# mimuz-can-v030.net
KiCad netlist of a schematic drawn in EAGLE
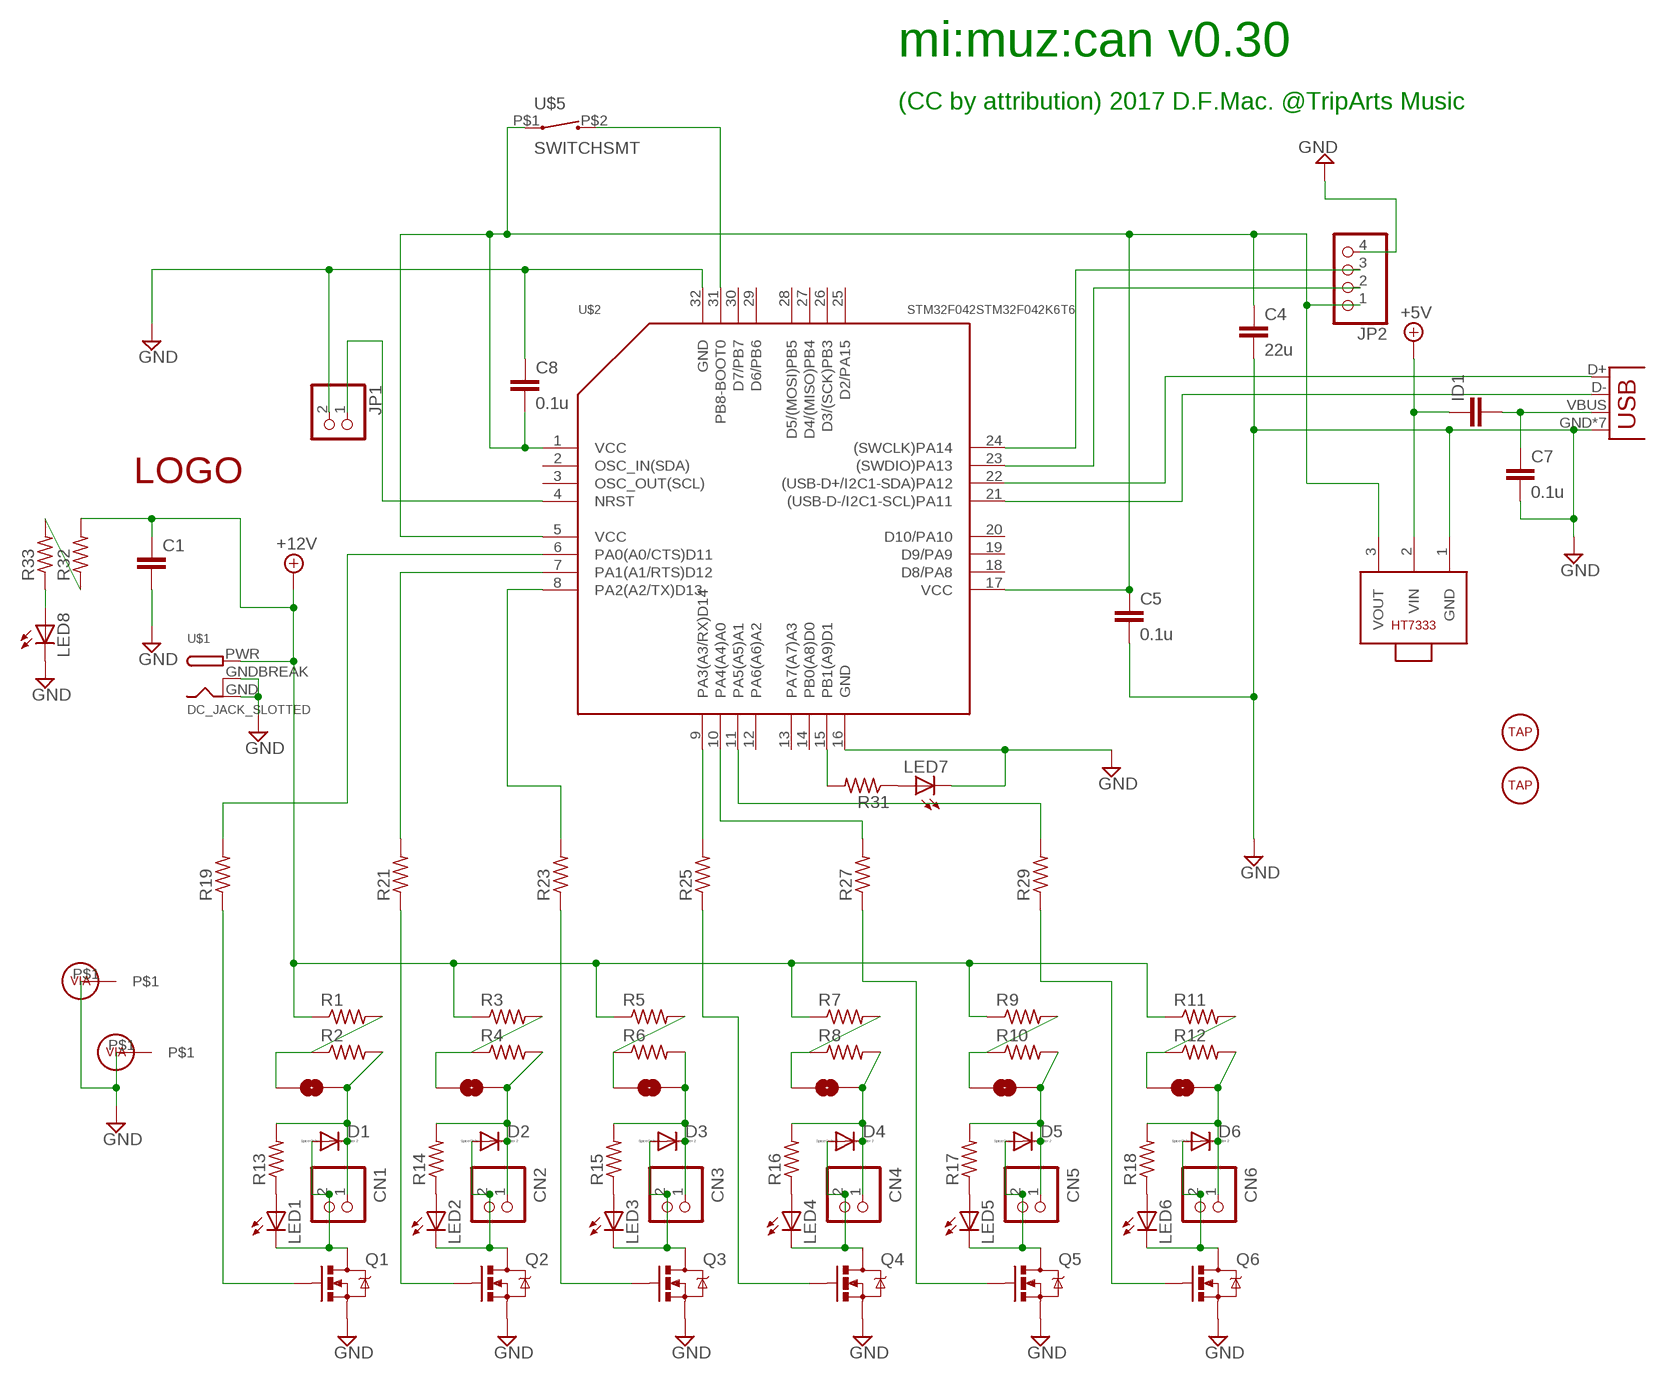
[diagram p0: schematic, sheet 1]

(export (version "E")
  (design (tool "Eeschema 10.0.6"))
  (components
    (comp (ref "C1")
      (value "C-EUC1206")
      (footprint "eagle-import:C1206")
      (libsource (lib "eagle-import") (part "C-EUC1206"))
    )
    (comp (ref "C4")
      (value "22u")
      (footprint "eagle-import:C0805")
      (libsource (lib "eagle-import") (part "C-EUC0805"))
    )
    (comp (ref "C5")
      (value "0.1u")
      (footprint "eagle-import:C0603")
      (libsource (lib "eagle-import") (part "C-EUC0603"))
    )
    (comp (ref "C7")
      (value "0.1u")
      (footprint "eagle-import:C0603")
      (libsource (lib "eagle-import") (part "C-EUC0603"))
    )
    (comp (ref "C8")
      (value "0.1u")
      (footprint "eagle-import:C0603")
      (libsource (lib "eagle-import") (part "C-EUC0603"))
    )
    (comp (ref "CN1")
      (value "B2B-PH-K-S")
      (footprint "eagle-import:B2B-PH-K-S")
      (libsource (lib "eagle-import") (part "B2B-PH-K-S"))
    )
    (comp (ref "CN2")
      (value "B2B-PH-K-S")
      (footprint "eagle-import:B2B-PH-K-S")
      (libsource (lib "eagle-import") (part "B2B-PH-K-S"))
    )
    (comp (ref "CN3")
      (value "B2B-PH-K-S")
      (footprint "eagle-import:B2B-PH-K-S")
      (libsource (lib "eagle-import") (part "B2B-PH-K-S"))
    )
    (comp (ref "CN4")
      (value "B2B-PH-K-S")
      (footprint "eagle-import:B2B-PH-K-S")
      (libsource (lib "eagle-import") (part "B2B-PH-K-S"))
    )
    (comp (ref "CN5")
      (value "B2B-PH-K-S")
      (footprint "eagle-import:B2B-PH-K-S")
      (libsource (lib "eagle-import") (part "B2B-PH-K-S"))
    )
    (comp (ref "CN6")
      (value "B2B-PH-K-S")
      (footprint "eagle-import:B2B-PH-K-S")
      (libsource (lib "eagle-import") (part "B2B-PH-K-S"))
    )
    (comp (ref "D1")
      (value "DIODE-DO214AC")
      (footprint "eagle-import:DO214AC")
      (libsource (lib "eagle-import") (part "DIODE-DO214AC"))
    )
    (comp (ref "D2")
      (value "DIODE-DO214AC")
      (footprint "eagle-import:DO214AC")
      (libsource (lib "eagle-import") (part "DIODE-DO214AC"))
    )
    (comp (ref "D3")
      (value "DIODE-DO214AC")
      (footprint "eagle-import:DO214AC")
      (libsource (lib "eagle-import") (part "DIODE-DO214AC"))
    )
    (comp (ref "D4")
      (value "DIODE-DO214AC")
      (footprint "eagle-import:DO214AC")
      (libsource (lib "eagle-import") (part "DIODE-DO214AC"))
    )
    (comp (ref "D5")
      (value "DIODE-DO214AC")
      (footprint "eagle-import:DO214AC")
      (libsource (lib "eagle-import") (part "DIODE-DO214AC"))
    )
    (comp (ref "D6")
      (value "DIODE-DO214AC")
      (footprint "eagle-import:DO214AC")
      (libsource (lib "eagle-import") (part "DIODE-DO214AC"))
    )
    (comp (ref "ID1")
      (value "C-EUC0805")
      (footprint "eagle-import:C0805")
      (libsource (lib "eagle-import") (part "C-EUC0805"))
    )
    (comp (ref "JP1")
      (value "PINHD-1X2")
      (footprint "eagle-import:1X02")
      (libsource (lib "eagle-import") (part "PINHD-1X2"))
    )
    (comp (ref "JP2")
      (value "PINHD-1X4")
      (footprint "eagle-import:1X04")
      (libsource (lib "eagle-import") (part "PINHD-1X4"))
    )
    (comp (ref "JP3")
      (value "JUMPER-SMT_2_NO_NO-SILK")
      (footprint "eagle-import:SMT-JUMPER_2_NO_NO-SILK")
      (libsource (lib "eagle-import") (part "JUMPER-SMT_2_NO_NO-SILK"))
    )
    (comp (ref "JP4")
      (value "USB-MICROB")
      (footprint "eagle-import:USB-MICROB")
      (libsource (lib "eagle-import") (part "USB-MICROB"))
    )
    (comp (ref "JP5")
      (value "JUMPER-SMT_2_NO_NO-SILK")
      (footprint "eagle-import:SMT-JUMPER_2_NO_NO-SILK")
      (libsource (lib "eagle-import") (part "JUMPER-SMT_2_NO_NO-SILK"))
    )
    (comp (ref "JP6")
      (value "JUMPER-SMT_2_NO_NO-SILK")
      (footprint "eagle-import:SMT-JUMPER_2_NO_NO-SILK")
      (libsource (lib "eagle-import") (part "JUMPER-SMT_2_NO_NO-SILK"))
    )
    (comp (ref "JP7")
      (value "JUMPER-SMT_2_NO_NO-SILK")
      (footprint "eagle-import:SMT-JUMPER_2_NO_NO-SILK")
      (libsource (lib "eagle-import") (part "JUMPER-SMT_2_NO_NO-SILK"))
    )
    (comp (ref "JP8")
      (value "JUMPER-SMT_2_NO_NO-SILK")
      (footprint "eagle-import:SMT-JUMPER_2_NO_NO-SILK")
      (libsource (lib "eagle-import") (part "JUMPER-SMT_2_NO_NO-SILK"))
    )
    (comp (ref "JP9")
      (value "JUMPER-SMT_2_NO_NO-SILK")
      (footprint "eagle-import:SMT-JUMPER_2_NO_NO-SILK")
      (libsource (lib "eagle-import") (part "JUMPER-SMT_2_NO_NO-SILK"))
    )
    (comp (ref "LED1")
      (value "LED3MM")
      (footprint "eagle-import:LED3MM")
      (libsource (lib "eagle-import") (part "LED3MM"))
    )
    (comp (ref "LED2")
      (value "LED3MM")
      (footprint "eagle-import:LED3MM")
      (libsource (lib "eagle-import") (part "LED3MM"))
    )
    (comp (ref "LED3")
      (value "LED3MM")
      (footprint "eagle-import:LED3MM")
      (libsource (lib "eagle-import") (part "LED3MM"))
    )
    (comp (ref "LED4")
      (value "LED3MM")
      (footprint "eagle-import:LED3MM")
      (libsource (lib "eagle-import") (part "LED3MM"))
    )
    (comp (ref "LED5")
      (value "LED3MM")
      (footprint "eagle-import:LED3MM")
      (libsource (lib "eagle-import") (part "LED3MM"))
    )
    (comp (ref "LED6")
      (value "LED3MM")
      (footprint "eagle-import:LED3MM")
      (libsource (lib "eagle-import") (part "LED3MM"))
    )
    (comp (ref "LED7")
      (value "LED3MM")
      (footprint "eagle-import:LED3MM")
      (libsource (lib "eagle-import") (part "LED3MM"))
    )
    (comp (ref "LED8")
      (value "LED3MM")
      (footprint "eagle-import:LED3MM")
      (libsource (lib "eagle-import") (part "LED3MM"))
    )
    (comp (ref "Q1")
      (value "MOSFET-NCHANNELSMD")
      (footprint "eagle-import:SOT23-3")
      (libsource (lib "eagle-import") (part "MOSFET-NCHANNELSMD"))
    )
    (comp (ref "Q2")
      (value "MOSFET-NCHANNELSMD")
      (footprint "eagle-import:SOT23-3")
      (libsource (lib "eagle-import") (part "MOSFET-NCHANNELSMD"))
    )
    (comp (ref "Q3")
      (value "MOSFET-NCHANNELSMD")
      (footprint "eagle-import:SOT23-3")
      (libsource (lib "eagle-import") (part "MOSFET-NCHANNELSMD"))
    )
    (comp (ref "Q4")
      (value "MOSFET-NCHANNELSMD")
      (footprint "eagle-import:SOT23-3")
      (libsource (lib "eagle-import") (part "MOSFET-NCHANNELSMD"))
    )
    (comp (ref "Q5")
      (value "MOSFET-NCHANNELSMD")
      (footprint "eagle-import:SOT23-3")
      (libsource (lib "eagle-import") (part "MOSFET-NCHANNELSMD"))
    )
    (comp (ref "Q6")
      (value "MOSFET-NCHANNELSMD")
      (footprint "eagle-import:SOT23-3")
      (libsource (lib "eagle-import") (part "MOSFET-NCHANNELSMD"))
    )
    (comp (ref "R1")
      (value "R-US_R2512")
      (footprint "eagle-import:R2512")
      (libsource (lib "eagle-import") (part "R-US_R2512"))
    )
    (comp (ref "R2")
      (value "R-US_R2512")
      (footprint "eagle-import:R2512")
      (libsource (lib "eagle-import") (part "R-US_R2512"))
    )
    (comp (ref "R3")
      (value "R-US_R2512")
      (footprint "eagle-import:R2512")
      (libsource (lib "eagle-import") (part "R-US_R2512"))
    )
    (comp (ref "R4")
      (value "R-US_R2512")
      (footprint "eagle-import:R2512")
      (libsource (lib "eagle-import") (part "R-US_R2512"))
    )
    (comp (ref "R5")
      (value "R-US_R2512")
      (footprint "eagle-import:R2512")
      (libsource (lib "eagle-import") (part "R-US_R2512"))
    )
    (comp (ref "R6")
      (value "R-US_R2512")
      (footprint "eagle-import:R2512")
      (libsource (lib "eagle-import") (part "R-US_R2512"))
    )
    (comp (ref "R7")
      (value "R-US_R2512")
      (footprint "eagle-import:R2512")
      (libsource (lib "eagle-import") (part "R-US_R2512"))
    )
    (comp (ref "R8")
      (value "R-US_R2512")
      (footprint "eagle-import:R2512")
      (libsource (lib "eagle-import") (part "R-US_R2512"))
    )
    (comp (ref "R9")
      (value "R-US_R2512")
      (footprint "eagle-import:R2512")
      (libsource (lib "eagle-import") (part "R-US_R2512"))
    )
    (comp (ref "R10")
      (value "R-US_R2512")
      (footprint "eagle-import:R2512")
      (libsource (lib "eagle-import") (part "R-US_R2512"))
    )
    (comp (ref "R11")
      (value "R-US_R2512")
      (footprint "eagle-import:R2512")
      (libsource (lib "eagle-import") (part "R-US_R2512"))
    )
    (comp (ref "R12")
      (value "R-US_R2512")
      (footprint "eagle-import:R2512")
      (libsource (lib "eagle-import") (part "R-US_R2512"))
    )
    (comp (ref "R13")
      (value "R-US_R0805")
      (footprint "eagle-import:R0805")
      (libsource (lib "eagle-import") (part "R-US_R0805"))
    )
    (comp (ref "R14")
      (value "R-US_R0805")
      (footprint "eagle-import:R0805")
      (libsource (lib "eagle-import") (part "R-US_R0805"))
    )
    (comp (ref "R15")
      (value "R-US_R0805")
      (footprint "eagle-import:R0805")
      (libsource (lib "eagle-import") (part "R-US_R0805"))
    )
    (comp (ref "R16")
      (value "R-US_R0805")
      (footprint "eagle-import:R0805")
      (libsource (lib "eagle-import") (part "R-US_R0805"))
    )
    (comp (ref "R17")
      (value "R-US_R0805")
      (footprint "eagle-import:R0805")
      (libsource (lib "eagle-import") (part "R-US_R0805"))
    )
    (comp (ref "R18")
      (value "R-US_R0805")
      (footprint "eagle-import:R0805")
      (libsource (lib "eagle-import") (part "R-US_R0805"))
    )
    (comp (ref "R19")
      (value "R-US_R0603")
      (footprint "eagle-import:R0603")
      (libsource (lib "eagle-import") (part "R-US_R0603"))
    )
    (comp (ref "R21")
      (value "R-US_R0603")
      (footprint "eagle-import:R0603")
      (libsource (lib "eagle-import") (part "R-US_R0603"))
    )
    (comp (ref "R23")
      (value "R-US_R0603")
      (footprint "eagle-import:R0603")
      (libsource (lib "eagle-import") (part "R-US_R0603"))
    )
    (comp (ref "R25")
      (value "R-US_R0603")
      (footprint "eagle-import:R0603")
      (libsource (lib "eagle-import") (part "R-US_R0603"))
    )
    (comp (ref "R27")
      (value "R-US_R0603")
      (footprint "eagle-import:R0603")
      (libsource (lib "eagle-import") (part "R-US_R0603"))
    )
    (comp (ref "R29")
      (value "R-US_R0603")
      (footprint "eagle-import:R0603")
      (libsource (lib "eagle-import") (part "R-US_R0603"))
    )
    (comp (ref "R31")
      (value "R-US_R0603")
      (footprint "eagle-import:R0603")
      (libsource (lib "eagle-import") (part "R-US_R0603"))
    )
    (comp (ref "R32")
      (value "R-US_R0805")
      (footprint "eagle-import:R0805")
      (libsource (lib "eagle-import") (part "R-US_R0805"))
    )
    (comp (ref "R33")
      (value "R-US_R0805")
      (footprint "eagle-import:R0805")
      (libsource (lib "eagle-import") (part "R-US_R0805"))
    )
    (comp (ref "U$1")
      (value "DC_JACK_SLOTTED")
      (footprint "eagle-import:DC_JACK_SLOTTED")
      (libsource (lib "eagle-import") (part "DC_JACK_SLOTTED"))
    )
    (comp (ref "U$2")
      (value "STM32F042STM32F042K6T6")
      (footprint "eagle-import:TQFP32")
      (libsource (lib "eagle-import") (part "STM32F042STM32F042K6T6"))
    )
    (comp (ref "U$3")
      (value "TAPHOLE")
      (footprint "eagle-import:TAPHOLE-3MM")
      (libsource (lib "eagle-import") (part "TAPHOLE"))
    )
    (comp (ref "U$4")
      (value "VIA")
      (footprint "eagle-import:VIA")
      (libsource (lib "eagle-import") (part "VIA"))
    )
    (comp (ref "U$5")
      (value "SWITCHSMT")
      (footprint "eagle-import:SWITCH-SMT-2_4_3")
      (libsource (lib "eagle-import") (part "SWITCHSMT"))
    )
    (comp (ref "U$6")
      (value "TAPHOLE")
      (footprint "eagle-import:TAPHOLE-3MM")
      (libsource (lib "eagle-import") (part "TAPHOLE"))
    )
    (comp (ref "U$7")
      (value "VIA")
      (footprint "eagle-import:VIA")
      (libsource (lib "eagle-import") (part "VIA"))
    )
    (comp (ref "U$12")
      (value "LOGOSMALL")
      (footprint "eagle-import:LOGO-SMALL")
      (libsource (lib "eagle-import") (part "LOGOSMALL"))
    )
    (comp (ref "U$14")
      (value "HT7333")
      (footprint "eagle-import:SOT89")
      (libsource (lib "eagle-import") (part "HT7333"))
    )
  )
  (nets
    (net (code "1") (name "+5V") (class "Default")
      (node (ref "ID1") (pin "1") (pinfunction "1_1") (pintype "passive"))
      (node (ref "U$14") (pin "2") (pinfunction "VIN_2") (pintype "bidirectional"))
    )
    (net (code "2") (name "+12V") (class "Default")
      (node (ref "C1") (pin "1") (pinfunction "1_1") (pintype "passive"))
      (node (ref "R1") (pin "1") (pinfunction "1_1") (pintype "passive"))
      (node (ref "R11") (pin "1") (pinfunction "1_1") (pintype "passive"))
      (node (ref "R3") (pin "1") (pinfunction "1_1") (pintype "passive"))
      (node (ref "R32") (pin "2") (pinfunction "2_2") (pintype "passive"))
      (node (ref "R5") (pin "1") (pinfunction "1_1") (pintype "passive"))
      (node (ref "R7") (pin "1") (pinfunction "1_1") (pintype "passive"))
      (node (ref "R9") (pin "1") (pinfunction "1_1") (pintype "passive"))
      (node (ref "U$1") (pin "PWR") (pinfunction "PWR_PWR") (pintype "power_in"))
    )
    (net (code "3") (name "GND") (class "Default")
      (node (ref "C1") (pin "2") (pinfunction "2_2") (pintype "passive"))
      (node (ref "C4") (pin "2") (pinfunction "2_2") (pintype "passive"))
      (node (ref "C5") (pin "2") (pinfunction "2_2") (pintype "passive"))
      (node (ref "C7") (pin "2") (pinfunction "2_2") (pintype "passive"))
      (node (ref "C8") (pin "1") (pinfunction "1_1") (pintype "passive"))
      (node (ref "JP1") (pin "2") (pinfunction "2_2") (pintype "passive"))
      (node (ref "JP2") (pin "4") (pinfunction "4_4") (pintype "passive"))
      (node (ref "JP4") (pin "GND") (pinfunction "GND_GND") (pintype "bidirectional"))
      (node (ref "JP4") (pin "MT1") (pinfunction "GND_MT1") (pintype "bidirectional"))
      (node (ref "JP4") (pin "MT3") (pinfunction "GND_MT3") (pintype "bidirectional"))
      (node (ref "JP4") (pin "P$2") (pinfunction "GND_P$2") (pintype "bidirectional"))
      (node (ref "JP4") (pin "P$4") (pinfunction "GND_P$4") (pintype "bidirectional"))
      (node (ref "JP4") (pin "P$5") (pinfunction "GND_P$5") (pintype "bidirectional"))
      (node (ref "JP4") (pin "P$6") (pinfunction "GND_P$6") (pintype "bidirectional"))
      (node (ref "LED7") (pin "K") (pinfunction "C_K") (pintype "passive"))
      (node (ref "LED8") (pin "K") (pinfunction "C_K") (pintype "passive"))
      (node (ref "Q1") (pin "2") (pinfunction "S_2") (pintype "passive"))
      (node (ref "Q2") (pin "2") (pinfunction "S_2") (pintype "passive"))
      (node (ref "Q3") (pin "2") (pinfunction "S_2") (pintype "passive"))
      (node (ref "Q4") (pin "2") (pinfunction "S_2") (pintype "passive"))
      (node (ref "Q5") (pin "2") (pinfunction "S_2") (pintype "passive"))
      (node (ref "Q6") (pin "2") (pinfunction "S_2") (pintype "passive"))
      (node (ref "U$1") (pin "GND") (pinfunction "GND_GND") (pintype "power_in"))
      (node (ref "U$1") (pin "GNDBREAK") (pinfunction "GNDBREAK_GNDBREAK") (pintype "power_in"))
      (node (ref "U$14") (pin "1") (pinfunction "GND_1") (pintype "bidirectional"))
      (node (ref "U$2") (pin "16") (pinfunction "GND_16") (pintype "bidirectional"))
      (node (ref "U$2") (pin "32") (pinfunction "GND_32") (pintype "bidirectional"))
      (node (ref "U$4") (pin "P$1") (pinfunction "P$1_P$1") (pintype "bidirectional"))
      (node (ref "U$7") (pin "P$1") (pinfunction "P$1_P$1") (pintype "bidirectional"))
    )
    (net (code "4") (name "Net-(C7-Pad1)") (class "Default")
      (node (ref "C7") (pin "1") (pinfunction "1_1") (pintype "passive"))
      (node (ref "ID1") (pin "2") (pinfunction "2_2") (pintype "passive"))
      (node (ref "JP4") (pin "VBUS") (pinfunction "VBUS_VBUS") (pintype "bidirectional"))
    )
    (net (code "5") (name "Net-(CN1-Pad1)") (class "Default")
      (node (ref "CN1") (pin "1") (pinfunction "1_1") (pintype "passive"))
      (node (ref "D1") (pin "C") (pinfunction "C_C") (pintype "passive"))
      (node (ref "JP3") (pin "2") (pinfunction "2_2") (pintype "passive"))
      (node (ref "R13") (pin "2") (pinfunction "2_2") (pintype "passive"))
      (node (ref "R2") (pin "2") (pinfunction "2_2") (pintype "passive"))
    )
    (net (code "6") (name "Net-(CN2-Pad1)") (class "Default")
      (node (ref "CN2") (pin "1") (pinfunction "1_1") (pintype "passive"))
      (node (ref "D2") (pin "C") (pinfunction "C_C") (pintype "passive"))
      (node (ref "JP5") (pin "2") (pinfunction "2_2") (pintype "passive"))
      (node (ref "R14") (pin "2") (pinfunction "2_2") (pintype "passive"))
      (node (ref "R4") (pin "2") (pinfunction "2_2") (pintype "passive"))
    )
    (net (code "7") (name "Net-(CN3-Pad1)") (class "Default")
      (node (ref "CN3") (pin "1") (pinfunction "1_1") (pintype "passive"))
      (node (ref "D3") (pin "C") (pinfunction "C_C") (pintype "passive"))
      (node (ref "JP6") (pin "2") (pinfunction "2_2") (pintype "passive"))
      (node (ref "R15") (pin "2") (pinfunction "2_2") (pintype "passive"))
      (node (ref "R6") (pin "2") (pinfunction "2_2") (pintype "passive"))
    )
    (net (code "8") (name "Net-(CN4-Pad1)") (class "Default")
      (node (ref "CN4") (pin "1") (pinfunction "1_1") (pintype "passive"))
      (node (ref "D4") (pin "C") (pinfunction "C_C") (pintype "passive"))
      (node (ref "JP7") (pin "2") (pinfunction "2_2") (pintype "passive"))
      (node (ref "R16") (pin "2") (pinfunction "2_2") (pintype "passive"))
      (node (ref "R8") (pin "2") (pinfunction "2_2") (pintype "passive"))
    )
    (net (code "9") (name "Net-(CN5-Pad1)") (class "Default")
      (node (ref "CN5") (pin "1") (pinfunction "1_1") (pintype "passive"))
      (node (ref "D5") (pin "C") (pinfunction "C_C") (pintype "passive"))
      (node (ref "JP8") (pin "2") (pinfunction "2_2") (pintype "passive"))
      (node (ref "R10") (pin "2") (pinfunction "2_2") (pintype "passive"))
      (node (ref "R17") (pin "2") (pinfunction "2_2") (pintype "passive"))
    )
    (net (code "10") (name "Net-(CN6-Pad1)") (class "Default")
      (node (ref "CN6") (pin "1") (pinfunction "1_1") (pintype "passive"))
      (node (ref "D6") (pin "C") (pinfunction "C_C") (pintype "passive"))
      (node (ref "JP9") (pin "2") (pinfunction "2_2") (pintype "passive"))
      (node (ref "R12") (pin "2") (pinfunction "2_2") (pintype "passive"))
      (node (ref "R18") (pin "2") (pinfunction "2_2") (pintype "passive"))
    )
    (net (code "11") (name "Net-(JP3-Pad1)") (class "Default")
      (node (ref "JP3") (pin "1") (pinfunction "1_1") (pintype "passive"))
      (node (ref "R1") (pin "2") (pinfunction "2_2") (pintype "passive"))
      (node (ref "R2") (pin "1") (pinfunction "1_1") (pintype "passive"))
    )
    (net (code "12") (name "Net-(JP5-Pad1)") (class "Default")
      (node (ref "JP5") (pin "1") (pinfunction "1_1") (pintype "passive"))
      (node (ref "R3") (pin "2") (pinfunction "2_2") (pintype "passive"))
      (node (ref "R4") (pin "1") (pinfunction "1_1") (pintype "passive"))
    )
    (net (code "13") (name "Net-(JP6-Pad1)") (class "Default")
      (node (ref "JP6") (pin "1") (pinfunction "1_1") (pintype "passive"))
      (node (ref "R5") (pin "2") (pinfunction "2_2") (pintype "passive"))
      (node (ref "R6") (pin "1") (pinfunction "1_1") (pintype "passive"))
    )
    (net (code "14") (name "Net-(JP7-Pad1)") (class "Default")
      (node (ref "JP7") (pin "1") (pinfunction "1_1") (pintype "passive"))
      (node (ref "R7") (pin "2") (pinfunction "2_2") (pintype "passive"))
      (node (ref "R8") (pin "1") (pinfunction "1_1") (pintype "passive"))
    )
    (net (code "15") (name "Net-(JP8-Pad1)") (class "Default")
      (node (ref "JP8") (pin "1") (pinfunction "1_1") (pintype "passive"))
      (node (ref "R10") (pin "1") (pinfunction "1_1") (pintype "passive"))
      (node (ref "R9") (pin "2") (pinfunction "2_2") (pintype "passive"))
    )
    (net (code "16") (name "Net-(JP9-Pad1)") (class "Default")
      (node (ref "JP9") (pin "1") (pinfunction "1_1") (pintype "passive"))
      (node (ref "R11") (pin "2") (pinfunction "2_2") (pintype "passive"))
      (node (ref "R12") (pin "1") (pinfunction "1_1") (pintype "passive"))
    )
    (net (code "17") (name "Net-(LED1-C)") (class "Default")
      (node (ref "CN1") (pin "2") (pinfunction "2_2") (pintype "passive"))
      (node (ref "D1") (pin "A") (pinfunction "A_A") (pintype "passive"))
      (node (ref "LED1") (pin "K") (pinfunction "C_K") (pintype "passive"))
      (node (ref "Q1") (pin "3") (pinfunction "D_3") (pintype "passive"))
    )
    (net (code "18") (name "Net-(LED1-PadA)") (class "Default")
      (node (ref "LED1") (pin "A") (pinfunction "A_A") (pintype "passive"))
      (node (ref "R13") (pin "1") (pinfunction "1_1") (pintype "passive"))
    )
    (net (code "19") (name "Net-(LED2-C)") (class "Default")
      (node (ref "CN2") (pin "2") (pinfunction "2_2") (pintype "passive"))
      (node (ref "D2") (pin "A") (pinfunction "A_A") (pintype "passive"))
      (node (ref "LED2") (pin "K") (pinfunction "C_K") (pintype "passive"))
      (node (ref "Q2") (pin "3") (pinfunction "D_3") (pintype "passive"))
    )
    (net (code "20") (name "Net-(LED2-PadA)") (class "Default")
      (node (ref "LED2") (pin "A") (pinfunction "A_A") (pintype "passive"))
      (node (ref "R14") (pin "1") (pinfunction "1_1") (pintype "passive"))
    )
    (net (code "21") (name "Net-(LED3-C)") (class "Default")
      (node (ref "CN3") (pin "2") (pinfunction "2_2") (pintype "passive"))
      (node (ref "D3") (pin "A") (pinfunction "A_A") (pintype "passive"))
      (node (ref "LED3") (pin "K") (pinfunction "C_K") (pintype "passive"))
      (node (ref "Q3") (pin "3") (pinfunction "D_3") (pintype "passive"))
    )
    (net (code "22") (name "Net-(LED3-PadA)") (class "Default")
      (node (ref "LED3") (pin "A") (pinfunction "A_A") (pintype "passive"))
      (node (ref "R15") (pin "1") (pinfunction "1_1") (pintype "passive"))
    )
    (net (code "23") (name "Net-(LED4-C)") (class "Default")
      (node (ref "CN4") (pin "2") (pinfunction "2_2") (pintype "passive"))
      (node (ref "D4") (pin "A") (pinfunction "A_A") (pintype "passive"))
      (node (ref "LED4") (pin "K") (pinfunction "C_K") (pintype "passive"))
      (node (ref "Q4") (pin "3") (pinfunction "D_3") (pintype "passive"))
    )
    (net (code "24") (name "Net-(LED4-PadA)") (class "Default")
      (node (ref "LED4") (pin "A") (pinfunction "A_A") (pintype "passive"))
      (node (ref "R16") (pin "1") (pinfunction "1_1") (pintype "passive"))
    )
    (net (code "25") (name "Net-(LED5-C)") (class "Default")
      (node (ref "CN5") (pin "2") (pinfunction "2_2") (pintype "passive"))
      (node (ref "D5") (pin "A") (pinfunction "A_A") (pintype "passive"))
      (node (ref "LED5") (pin "K") (pinfunction "C_K") (pintype "passive"))
      (node (ref "Q5") (pin "3") (pinfunction "D_3") (pintype "passive"))
    )
    (net (code "26") (name "Net-(LED5-PadA)") (class "Default")
      (node (ref "LED5") (pin "A") (pinfunction "A_A") (pintype "passive"))
      (node (ref "R17") (pin "1") (pinfunction "1_1") (pintype "passive"))
    )
    (net (code "27") (name "Net-(LED6-C)") (class "Default")
      (node (ref "CN6") (pin "2") (pinfunction "2_2") (pintype "passive"))
      (node (ref "D6") (pin "A") (pinfunction "A_A") (pintype "passive"))
      (node (ref "LED6") (pin "K") (pinfunction "C_K") (pintype "passive"))
      (node (ref "Q6") (pin "3") (pinfunction "D_3") (pintype "passive"))
    )
    (net (code "28") (name "Net-(LED6-PadA)") (class "Default")
      (node (ref "LED6") (pin "A") (pinfunction "A_A") (pintype "passive"))
      (node (ref "R18") (pin "1") (pinfunction "1_1") (pintype "passive"))
    )
    (net (code "29") (name "Net-(LED7-PadA)") (class "Default")
      (node (ref "LED7") (pin "A") (pinfunction "A_A") (pintype "passive"))
      (node (ref "R31") (pin "1") (pinfunction "1_1") (pintype "passive"))
    )
    (net (code "30") (name "Net-(LED8-PadA)") (class "Default")
      (node (ref "LED8") (pin "A") (pinfunction "A_A") (pintype "passive"))
      (node (ref "R33") (pin "1") (pinfunction "1_1") (pintype "passive"))
    )
    (net (code "31") (name "Net-(Q1-G)") (class "Default")
      (node (ref "Q1") (pin "1") (pinfunction "G_1") (pintype "passive"))
      (node (ref "R19") (pin "1") (pinfunction "1_1") (pintype "passive"))
    )
    (net (code "32") (name "Net-(Q2-G)") (class "Default")
      (node (ref "Q2") (pin "1") (pinfunction "G_1") (pintype "passive"))
      (node (ref "R21") (pin "1") (pinfunction "1_1") (pintype "passive"))
    )
    (net (code "33") (name "Net-(Q3-G)") (class "Default")
      (node (ref "Q3") (pin "1") (pinfunction "G_1") (pintype "passive"))
      (node (ref "R23") (pin "1") (pinfunction "1_1") (pintype "passive"))
    )
    (net (code "34") (name "Net-(Q4-G)") (class "Default")
      (node (ref "Q4") (pin "1") (pinfunction "G_1") (pintype "passive"))
      (node (ref "R25") (pin "1") (pinfunction "1_1") (pintype "passive"))
    )
    (net (code "35") (name "Net-(Q5-G)") (class "Default")
      (node (ref "Q5") (pin "1") (pinfunction "G_1") (pintype "passive"))
      (node (ref "R27") (pin "1") (pinfunction "1_1") (pintype "passive"))
    )
    (net (code "36") (name "Net-(Q6-G)") (class "Default")
      (node (ref "Q6") (pin "1") (pinfunction "G_1") (pintype "passive"))
      (node (ref "R29") (pin "1") (pinfunction "1_1") (pintype "passive"))
    )
    (net (code "37") (name "Net-(R32-Pad1)") (class "Default")
      (node (ref "R32") (pin "1") (pinfunction "1_1") (pintype "passive"))
      (node (ref "R33") (pin "2") (pinfunction "2_2") (pintype "passive"))
    )
    (net (code "38") (name "Net-(U$2-(SWCLK)PA14)") (class "Default")
      (node (ref "JP2") (pin "3") (pinfunction "3_3") (pintype "passive"))
      (node (ref "U$2") (pin "24") (pinfunction "(SWCLK)PA14_24") (pintype "bidirectional"))
    )
    (net (code "39") (name "Net-(U$2-(SWDIO)PA13)") (class "Default")
      (node (ref "JP2") (pin "2") (pinfunction "2_2") (pintype "passive"))
      (node (ref "U$2") (pin "23") (pinfunction "(SWDIO)PA13_23") (pintype "bidirectional"))
    )
    (net (code "40") (name "Net-(U$2-(USB-D+{slash}I2C1-SDA)PA12)") (class "Default")
      (node (ref "JP4") (pin "D+") (pinfunction "D+_D+") (pintype "bidirectional"))
      (node (ref "U$2") (pin "22") (pinfunction "(USB-D+/I2C1-SDA)PA12_22") (pintype "bidirectional"))
    )
    (net (code "41") (name "Net-(U$2-(USB-D-{slash}I2C1-SCL)PA11)") (class "Default")
      (node (ref "JP4") (pin "D-") (pinfunction "D-_D-") (pintype "bidirectional"))
      (node (ref "U$2") (pin "21") (pinfunction "(USB-D-/I2C1-SCL)PA11_21") (pintype "bidirectional"))
    )
    (net (code "42") (name "Net-(U$2-NRST)") (class "Default")
      (node (ref "JP1") (pin "1") (pinfunction "1_1") (pintype "passive"))
      (node (ref "U$2") (pin "4") (pinfunction "NRST_4") (pintype "bidirectional"))
    )
    (net (code "43") (name "Net-(U$2-PA0(A0{slash}CTS)D11)") (class "Default")
      (node (ref "R19") (pin "2") (pinfunction "2_2") (pintype "passive"))
      (node (ref "U$2") (pin "6") (pinfunction "PA0(A0/CTS)D11_6") (pintype "bidirectional"))
    )
    (net (code "44") (name "Net-(U$2-PA1(A1{slash}RTS)D12)") (class "Default")
      (node (ref "R21") (pin "2") (pinfunction "2_2") (pintype "passive"))
      (node (ref "U$2") (pin "7") (pinfunction "PA1(A1/RTS)D12_7") (pintype "bidirectional"))
    )
    (net (code "45") (name "Net-(U$2-PA2(A2{slash}TX)D13)") (class "Default")
      (node (ref "R23") (pin "2") (pinfunction "2_2") (pintype "passive"))
      (node (ref "U$2") (pin "8") (pinfunction "PA2(A2/TX)D13_8") (pintype "bidirectional"))
    )
    (net (code "46") (name "Net-(U$2-PA3(A3{slash}RX)D14)") (class "Default")
      (node (ref "R25") (pin "2") (pinfunction "2_2") (pintype "passive"))
      (node (ref "U$2") (pin "9") (pinfunction "PA3(A3/RX)D14_9") (pintype "bidirectional"))
    )
    (net (code "47") (name "Net-(U$2-PA4(A4)A0)") (class "Default")
      (node (ref "R27") (pin "2") (pinfunction "2_2") (pintype "passive"))
      (node (ref "U$2") (pin "10") (pinfunction "PA4(A4)A0_10") (pintype "bidirectional"))
    )
    (net (code "48") (name "Net-(U$2-PA5(A5)A1)") (class "Default")
      (node (ref "R29") (pin "2") (pinfunction "2_2") (pintype "passive"))
      (node (ref "U$2") (pin "11") (pinfunction "PA5(A5)A1_11") (pintype "bidirectional"))
    )
    (net (code "49") (name "Net-(U$2-PB1(A9)D1)") (class "Default")
      (node (ref "R31") (pin "2") (pinfunction "2_2") (pintype "passive"))
      (node (ref "U$2") (pin "15") (pinfunction "PB1(A9)D1_15") (pintype "bidirectional"))
    )
    (net (code "50") (name "Net-(U$2-PB8-BOOT0)") (class "Default")
      (node (ref "U$2") (pin "31") (pinfunction "PB8-BOOT0_31") (pintype "bidirectional"))
      (node (ref "U$5") (pin "P$2") (pinfunction "2_P$2") (pintype "passive"))
    )
    (net (code "51") (name "Net-(U$14-VOUT)") (class "Default")
      (node (ref "C4") (pin "1") (pinfunction "1_1") (pintype "passive"))
      (node (ref "C5") (pin "1") (pinfunction "1_1") (pintype "passive"))
      (node (ref "C8") (pin "2") (pinfunction "2_2") (pintype "passive"))
      (node (ref "JP2") (pin "1") (pinfunction "1_1") (pintype "passive"))
      (node (ref "U$14") (pin "3") (pinfunction "VOUT_3") (pintype "bidirectional"))
      (node (ref "U$2") (pin "1") (pinfunction "VCC_1") (pintype "bidirectional"))
      (node (ref "U$2") (pin "17") (pinfunction "VCC_17") (pintype "bidirectional"))
      (node (ref "U$2") (pin "5") (pinfunction "VCC_5") (pintype "bidirectional"))
      (node (ref "U$5") (pin "P$1") (pinfunction "1_P$1") (pintype "passive"))
    )
    (net (code "52") (name "unconnected-(U$2-D2{slash}PA15-Pad25)") (class "Default")
      (node (ref "U$2") (pin "25") (pinfunction "D2/PA15_25") (pintype "bidirectional"))
    )
    (net (code "53") (name "unconnected-(U$2-D3{slash}(SCK)PB3-Pad26)") (class "Default")
      (node (ref "U$2") (pin "26") (pinfunction "D3/(SCK)PB3_26") (pintype "bidirectional"))
    )
    (net (code "54") (name "unconnected-(U$2-D4{slash}(MISO)PB4-Pad27)") (class "Default")
      (node (ref "U$2") (pin "27") (pinfunction "D4/(MISO)PB4_27") (pintype "bidirectional"))
    )
    (net (code "55") (name "unconnected-(U$2-D5{slash}(MOSI)PB5-Pad28)") (class "Default")
      (node (ref "U$2") (pin "28") (pinfunction "D5/(MOSI)PB5_28") (pintype "bidirectional"))
    )
    (net (code "56") (name "unconnected-(U$2-D6{slash}PB6-Pad29)") (class "Default")
      (node (ref "U$2") (pin "29") (pinfunction "D6/PB6_29") (pintype "bidirectional"))
    )
    (net (code "57") (name "unconnected-(U$2-D7{slash}PB7-Pad30)") (class "Default")
      (node (ref "U$2") (pin "30") (pinfunction "D7/PB7_30") (pintype "bidirectional"))
    )
    (net (code "58") (name "unconnected-(U$2-D8{slash}PA8-Pad18)") (class "Default")
      (node (ref "U$2") (pin "18") (pinfunction "D8/PA8_18") (pintype "bidirectional"))
    )
    (net (code "59") (name "unconnected-(U$2-D9{slash}PA9-Pad19)") (class "Default")
      (node (ref "U$2") (pin "19") (pinfunction "D9/PA9_19") (pintype "bidirectional"))
    )
    (net (code "60") (name "unconnected-(U$2-D10{slash}PA10-Pad20)") (class "Default")
      (node (ref "U$2") (pin "20") (pinfunction "D10/PA10_20") (pintype "bidirectional"))
    )
    (net (code "61") (name "unconnected-(U$2-OSC_IN(SDA)-Pad2)") (class "Default")
      (node (ref "U$2") (pin "2") (pinfunction "OSC_IN(SDA)_2") (pintype "bidirectional"))
    )
    (net (code "62") (name "unconnected-(U$2-OSC_OUT(SCL)-Pad3)") (class "Default")
      (node (ref "U$2") (pin "3") (pinfunction "OSC_OUT(SCL)_3") (pintype "bidirectional"))
    )
    (net (code "63") (name "unconnected-(U$2-PA6(A6)A2-Pad12)") (class "Default")
      (node (ref "U$2") (pin "12") (pinfunction "PA6(A6)A2_12") (pintype "bidirectional"))
    )
    (net (code "64") (name "unconnected-(U$2-PA7(A7)A3-Pad13)") (class "Default")
      (node (ref "U$2") (pin "13") (pinfunction "PA7(A7)A3_13") (pintype "bidirectional"))
    )
    (net (code "65") (name "unconnected-(U$2-PB0(A8)D0-Pad14)") (class "Default")
      (node (ref "U$2") (pin "14") (pinfunction "PB0(A8)D0_14") (pintype "bidirectional"))
    )
  )
)
